# Leak_Sensor_Schematic.net
KiCad netlist of a schematic drawn in Altium Designer
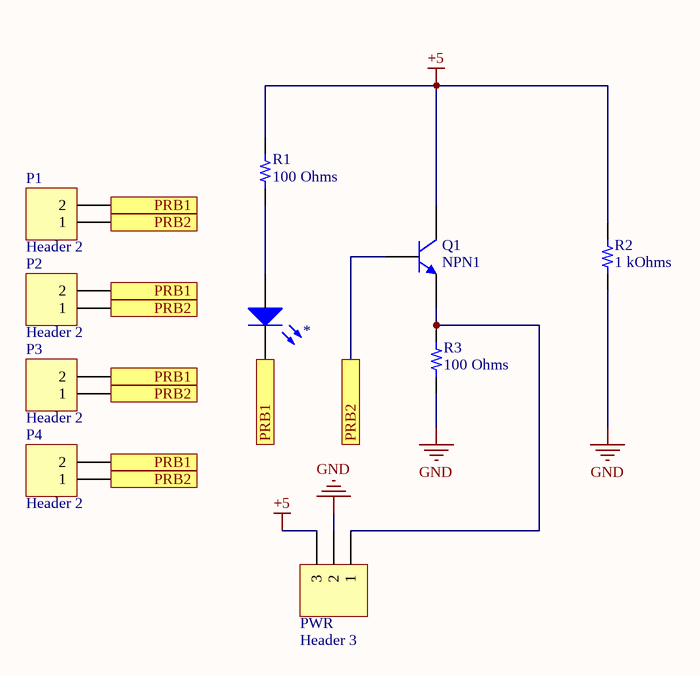
[diagram p0: Leak Sensor Schematic.SchDoc]

(export (version "E")
  (design (tool "Eeschema 10.0.6"))
  (components
    (comp (ref "*")
      (value "THT_LED")
      (footprint "THT_LED")
      (libsource (lib "Miscellaneous Devices") (part "THT_LED"))
    )
    (comp (ref "P1")
      (value "Header 2")
      (footprint "HDR1X2")
      (description "Header, 2-Pin")
      (fields (field (name "PUBLISHER") "Altium Limited"))
      (libsource (lib "Miscellaneous Connectors") (part "Header 2"))
    )
    (comp (ref "P2")
      (value "Header 2")
      (footprint "HDR1X2")
      (description "Header, 2-Pin")
      (fields (field (name "PUBLISHER") "Altium Limited"))
      (libsource (lib "Miscellaneous Connectors") (part "Header 2"))
    )
    (comp (ref "P3")
      (value "Header 2")
      (footprint "HDR1X2")
      (description "Header, 2-Pin")
      (fields (field (name "PUBLISHER") "Altium Limited"))
      (libsource (lib "Miscellaneous Connectors") (part "Header 2"))
    )
    (comp (ref "P4")
      (value "Header 2")
      (footprint "HDR1X2")
      (description "Header, 2-Pin")
      (fields (field (name "PUBLISHER") "Altium Limited"))
      (libsource (lib "Miscellaneous Connectors") (part "Header 2"))
    )
    (comp (ref "PWR")
      (value "Header 3")
      (footprint "HDR1X3")
      (description "Header, 3-Pin")
      (fields (field (name "PUBLISHER") "Altium Limited"))
      (libsource (lib "Miscellaneous Connectors") (part "Header 3"))
    )
    (comp (ref "Q1")
      (value "NPN1")
      (footprint "TO-92A")
      (description "NPN Bipolar Transistor")
      (fields (field (name "PUBLISHER") "Altium Limited"))
      (libsource (lib "Miscellaneous Devices") (part "NPN1"))
    )
    (comp (ref "R1")
      (value "100 Ohms")
      (footprint "RES 1210_3225")
      (description "RES 100 OHM 5% 1/2W 1210")
      (fields
        (field (name "PART NUMBER") "RMCF1210JT100R")
        (field (name "MANUFACTURER") "Stackpole Electronics Inc")
      )
      (libsource (lib "Celestial Altium Library - altium_library") (part "Resistor"))
    )
    (comp (ref "R2")
      (value "1 kOhms")
      (footprint "RES 1210_3225")
      (description "RES 1K OHM 5% 1/3W 1210")
      (fields
        (field (name "PART NUMBER") "RMCF1210JT1K00")
        (field (name "MANUFACTURER") "Stackpole Electronics Inc")
      )
      (libsource (lib "Celestial Altium Library - altium_library") (part "Resistor"))
    )
    (comp (ref "R3")
      (value "100 Ohms")
      (footprint "RES 1210_3225")
      (description "RES 100 OHM 5% 1/2W 1210")
      (fields
        (field (name "PART NUMBER") "RMCF1210JT100R")
        (field (name "MANUFACTURER") "Stackpole Electronics Inc")
      )
      (libsource (lib "Celestial Altium Library - altium_library") (part "Resistor"))
    )
  )
  (nets
    (net (code "1") (name "+5") (class "Default")
      (node (ref "PWR") (pin "3") (pinfunction "3_3") (pintype "passive"))
      (node (ref "Q1") (pin "1") (pinfunction "C_1") (pintype "passive"))
      (node (ref "R1") (pin "2") (pinfunction "2_2") (pintype "passive"))
      (node (ref "R2") (pin "2") (pinfunction "2_2") (pintype "passive"))
    )
    (net (code "2") (name "/PRB1") (class "Default")
      (node (ref "*") (pin "2") (pinfunction "K_2") (pintype "passive"))
      (node (ref "P1") (pin "2") (pinfunction "2_2") (pintype "passive"))
      (node (ref "P2") (pin "2") (pinfunction "2_2") (pintype "passive"))
      (node (ref "P3") (pin "2") (pinfunction "2_2") (pintype "passive"))
      (node (ref "P4") (pin "2") (pinfunction "2_2") (pintype "passive"))
    )
    (net (code "3") (name "/PRB2") (class "Default")
      (node (ref "P1") (pin "1") (pinfunction "1_1") (pintype "passive"))
      (node (ref "P2") (pin "1") (pinfunction "1_1") (pintype "passive"))
      (node (ref "P3") (pin "1") (pinfunction "1_1") (pintype "passive"))
      (node (ref "P4") (pin "1") (pinfunction "1_1") (pintype "passive"))
      (node (ref "Q1") (pin "2") (pinfunction "B_2") (pintype "passive"))
    )
    (net (code "4") (name "GND") (class "Default")
      (node (ref "PWR") (pin "2") (pinfunction "2_2") (pintype "passive"))
      (node (ref "R2") (pin "1") (pinfunction "1_1") (pintype "passive"))
      (node (ref "R3") (pin "1") (pinfunction "1_1") (pintype "passive"))
    )
    (net (code "5") (name "Net-(*-A)") (class "Default")
      (node (ref "*") (pin "1") (pinfunction "A_1") (pintype "passive"))
      (node (ref "R1") (pin "1") (pinfunction "1_1") (pintype "passive"))
    )
    (net (code "6") (name "Net-(Q1-E)") (class "Default")
      (node (ref "PWR") (pin "1") (pinfunction "1_1") (pintype "passive"))
      (node (ref "Q1") (pin "3") (pinfunction "E_3") (pintype "passive"))
      (node (ref "R3") (pin "2") (pinfunction "2_2") (pintype "passive"))
    )
  )
)
